# Dog_Fountain.net
KiCad netlist of a schematic drawn in EAGLE
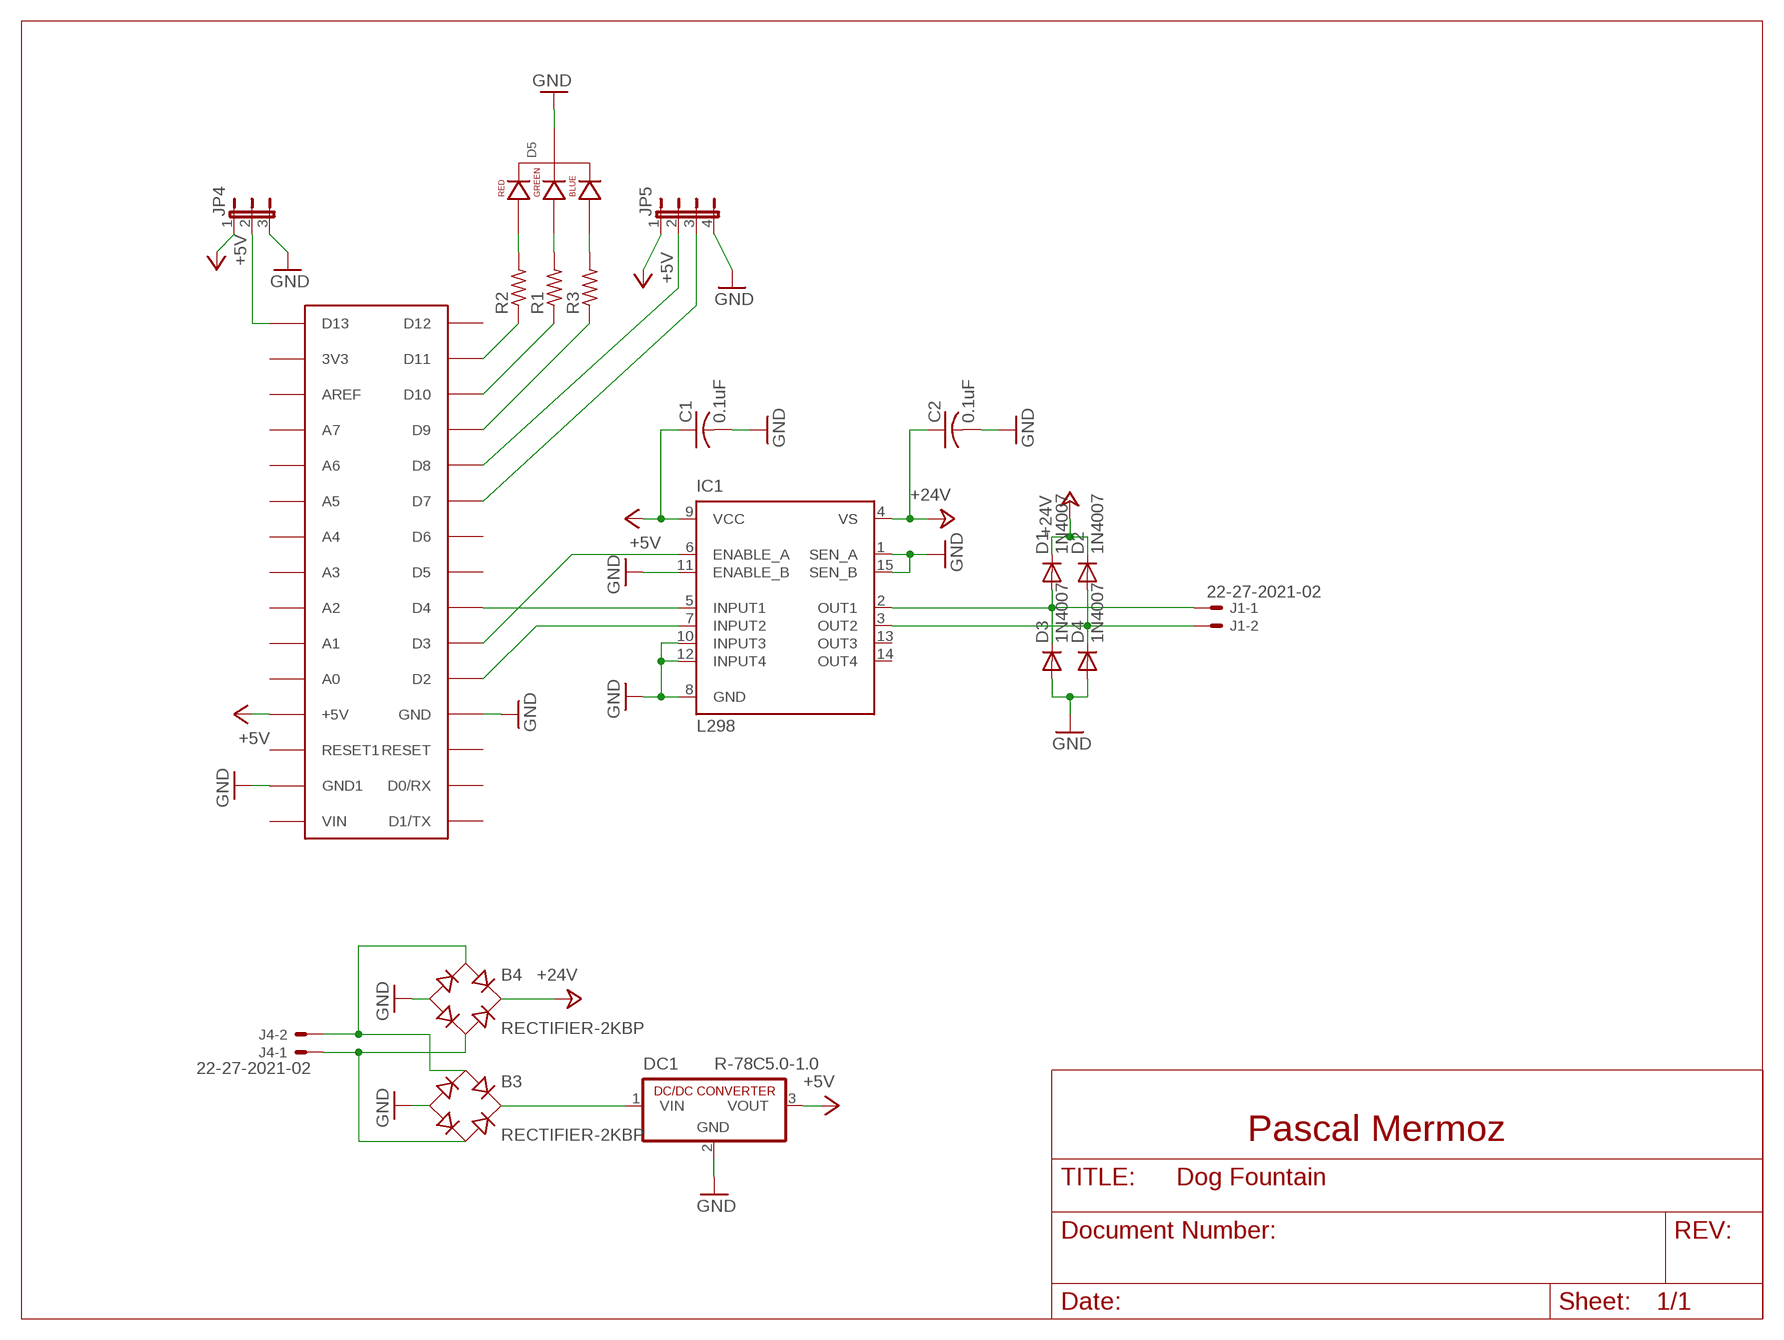
[diagram p0: schematic, sheet 1]

(export (version "E")
  (design (tool "Eeschema 10.0.6"))
  (components
    (comp (ref "B3")
      (value "RECTIFIER-2KBP")
      (footprint "eagle-import:2KBP")
      (fields (field (name "MPN") "KBP202G"))
      (libsource (lib "eagle-import") (part "RECTIFIER-2KBP"))
    )
    (comp (ref "B4")
      (value "RECTIFIER-2KBP")
      (footprint "eagle-import:2KBP")
      (fields (field (name "MPN") "KBP202G"))
      (libsource (lib "eagle-import") (part "RECTIFIER-2KBP"))
    )
    (comp (ref "C1")
      (value "0.1uF")
      (footprint "eagle-import:C050-024X044")
      (fields (field (name "MPN") "C317C104K5R5TA"))
      (libsource (lib "eagle-import") (part "C-US050-024X044"))
    )
    (comp (ref "C2")
      (value "0.1uF")
      (footprint "eagle-import:C050-024X044")
      (fields (field (name "MPN") "C317C104K5R5TA"))
      (libsource (lib "eagle-import") (part "C-US050-024X044"))
    )
    (comp (ref "D1")
      (value "1N4007")
      (footprint "eagle-import:DO41-10")
      (fields (field (name "MPN") "KBP202G"))
      (libsource (lib "eagle-import") (part "DIODE-DO41-10"))
    )
    (comp (ref "D2")
      (value "1N4007")
      (footprint "eagle-import:DO41-10")
      (fields (field (name "MPN") "KBP202G"))
      (libsource (lib "eagle-import") (part "DIODE-DO41-10"))
    )
    (comp (ref "D3")
      (value "1N4007")
      (footprint "eagle-import:DO41-10")
      (fields (field (name "MPN") "KBP202G"))
      (libsource (lib "eagle-import") (part "DIODE-DO41-10"))
    )
    (comp (ref "D4")
      (value "1N4007")
      (footprint "eagle-import:DO41-10")
      (fields (field (name "MPN") "KBP202G"))
      (libsource (lib "eagle-import") (part "DIODE-DO41-10"))
    )
    (comp (ref "D5")
      (value "LED-RGB-CC-THRUDIFFUSE")
      (footprint "eagle-import:LED-RGB-THRU")
      (libsource (lib "eagle-import") (part "LED-RGB-CC-THRUDIFFUSE"))
    )
    (comp (ref "DC1")
      (value "R-78C5.0-1.0")
      (footprint "eagle-import:SIP3")
      (fields (field (name "MPN") "OKI-78SR-5/1.5-W36-C"))
      (libsource (lib "eagle-import") (part "R-78C-1.05.0"))
    )
    (comp (ref "IC1")
      (value "L298")
      (footprint "eagle-import:MULTIWATT-15")
      (fields (field (name "MPN") "L298N"))
      (libsource (lib "eagle-import") (part "L298"))
    )
    (comp (ref "J1")
      (value "22-27-2021-02")
      (footprint "eagle-import:6410-02")
      (libsource (lib "eagle-import") (part "22-?-0227-2021"))
    )
    (comp (ref "J4")
      (value "22-27-2021-02")
      (footprint "eagle-import:6410-02")
      (libsource (lib "eagle-import") (part "22-?-0227-2021"))
    )
    (comp (ref "JP4")
      (value "JP2E")
      (footprint "eagle-import:JP2")
      (libsource (lib "eagle-import") (part "JP2E"))
    )
    (comp (ref "JP5")
      (value "JP4E")
      (footprint "eagle-import:JP4")
      (libsource (lib "eagle-import") (part "JP4E"))
    )
    (comp (ref "R1")
      (value "R-US_0204/2V")
      (footprint "eagle-import:0204V")
      (libsource (lib "eagle-import") (part "R-US_0204/2V"))
    )
    (comp (ref "R2")
      (value "R-US_0204/2V")
      (footprint "eagle-import:0204V")
      (libsource (lib "eagle-import") (part "R-US_0204/2V"))
    )
    (comp (ref "R3")
      (value "R-US_0204/2V")
      (footprint "eagle-import:0204V")
      (libsource (lib "eagle-import") (part "R-US_0204/2V"))
    )
    (comp (ref "U$1")
      (value "ARDUINONANO")
      (footprint "eagle-import:PDIP-32")
      (fields (field (name "MPN") "A000005"))
      (libsource (lib "eagle-import") (part "ARDUINONANO"))
    )
  )
  (nets
    (net (code "1") (name "+5V") (class "Default")
      (node (ref "C1") (pin "1") (pinfunction "1_1") (pintype "passive"))
      (node (ref "DC1") (pin "3") (pinfunction "VOUT_3") (pintype "passive"))
      (node (ref "IC1") (pin "9") (pinfunction "VCC_9") (pintype "power_in"))
      (node (ref "JP4") (pin "1") (pinfunction "1_1") (pintype "passive"))
      (node (ref "JP5") (pin "1") (pinfunction "1_1") (pintype "passive"))
      (node (ref "U$1") (pin "+5V") (pinfunction "+5V_+5V") (pintype "bidirectional"))
    )
    (net (code "2") (name "+24V") (class "Default")
      (node (ref "B4") (pin "+") (pinfunction "+_+") (pintype "passive"))
      (node (ref "C2") (pin "1") (pinfunction "1_1") (pintype "passive"))
      (node (ref "D1") (pin "C") (pinfunction "C_C") (pintype "passive"))
      (node (ref "D2") (pin "C") (pinfunction "C_C") (pintype "passive"))
      (node (ref "IC1") (pin "4") (pinfunction "VS_4") (pintype "power_in"))
    )
    (net (code "3") (name "GND") (class "Default")
      (node (ref "B3") (pin "-") (pinfunction "-_-") (pintype "passive"))
      (node (ref "B4") (pin "-") (pinfunction "-_-") (pintype "passive"))
      (node (ref "C1") (pin "2") (pinfunction "2_2") (pintype "passive"))
      (node (ref "C2") (pin "2") (pinfunction "2_2") (pintype "passive"))
      (node (ref "D3") (pin "A") (pinfunction "A_A") (pintype "passive"))
      (node (ref "D4") (pin "A") (pinfunction "A_A") (pintype "passive"))
      (node (ref "D5") (pin "2") (pinfunction "CATHODE_2") (pintype "bidirectional"))
      (node (ref "DC1") (pin "2") (pinfunction "GND_2") (pintype "passive"))
      (node (ref "IC1") (pin "1") (pinfunction "SEN_A_1") (pintype "input"))
      (node (ref "IC1") (pin "10") (pinfunction "INPUT3_10") (pintype "input"))
      (node (ref "IC1") (pin "11") (pinfunction "ENABLE_B_11") (pintype "input"))
      (node (ref "IC1") (pin "12") (pinfunction "INPUT4_12") (pintype "input"))
      (node (ref "IC1") (pin "15") (pinfunction "SEN_B_15") (pintype "input"))
      (node (ref "IC1") (pin "8") (pinfunction "GND_8") (pintype "power_in"))
      (node (ref "JP4") (pin "3") (pinfunction "3_3") (pintype "passive"))
      (node (ref "JP5") (pin "4") (pinfunction "4_4") (pintype "passive"))
      (node (ref "U$1") (pin "GND") (pinfunction "GND_GND") (pintype "bidirectional"))
      (node (ref "U$1") (pin "GND1") (pinfunction "GND1_GND1") (pintype "bidirectional"))
    )
    (net (code "4") (name "Net-(D5-BLUE_CATHODE)") (class "Default")
      (node (ref "D5") (pin "4") (pinfunction "BLUE_CATHODE_4") (pintype "bidirectional"))
      (node (ref "R3") (pin "2") (pinfunction "2_2") (pintype "passive"))
    )
    (net (code "5") (name "Net-(D5-GREEN_CATHODE)") (class "Default")
      (node (ref "D5") (pin "3") (pinfunction "GREEN_CATHODE_3") (pintype "bidirectional"))
      (node (ref "R1") (pin "2") (pinfunction "2_2") (pintype "passive"))
    )
    (net (code "6") (name "Net-(D5-RED_CATHODE)") (class "Default")
      (node (ref "D5") (pin "1") (pinfunction "RED_CATHODE_1") (pintype "bidirectional"))
      (node (ref "R2") (pin "2") (pinfunction "2_2") (pintype "passive"))
    )
    (net (code "7") (name "Net-(DC1-VIN)") (class "Default")
      (node (ref "B3") (pin "+") (pinfunction "+_+") (pintype "passive"))
      (node (ref "DC1") (pin "1") (pinfunction "VIN_1") (pintype "passive"))
    )
    (net (code "8") (name "Net-(IC1-ENABLE_A)") (class "Default")
      (node (ref "IC1") (pin "6") (pinfunction "ENABLE_A_6") (pintype "input"))
      (node (ref "U$1") (pin "D3") (pinfunction "D3_D3") (pintype "bidirectional"))
    )
    (net (code "9") (name "Net-(IC1-INPUT1)") (class "Default")
      (node (ref "IC1") (pin "5") (pinfunction "INPUT1_5") (pintype "input"))
      (node (ref "U$1") (pin "D4") (pinfunction "D4_D4") (pintype "bidirectional"))
    )
    (net (code "10") (name "Net-(IC1-INPUT2)") (class "Default")
      (node (ref "IC1") (pin "7") (pinfunction "INPUT2_7") (pintype "input"))
      (node (ref "U$1") (pin "D2") (pinfunction "D2_D2") (pintype "bidirectional"))
    )
    (net (code "11") (name "Net-(IC1-OUT1)") (class "Default")
      (node (ref "D1") (pin "A") (pinfunction "A_A") (pintype "passive"))
      (node (ref "D3") (pin "C") (pinfunction "C_C") (pintype "passive"))
      (node (ref "IC1") (pin "2") (pinfunction "OUT1_2") (pintype "output"))
      (node (ref "J1") (pin "1") (pinfunction "S_1") (pintype "passive"))
    )
    (net (code "12") (name "Net-(IC1-OUT2)") (class "Default")
      (node (ref "D2") (pin "A") (pinfunction "A_A") (pintype "passive"))
      (node (ref "D4") (pin "C") (pinfunction "C_C") (pintype "passive"))
      (node (ref "IC1") (pin "3") (pinfunction "OUT2_3") (pintype "output"))
      (node (ref "J1") (pin "2") (pinfunction "S_2") (pintype "passive"))
    )
    (net (code "13") (name "Net-(J4A-S)") (class "Default")
      (node (ref "B3") (pin "AC2") (pinfunction "AC2_AC2") (pintype "passive"))
      (node (ref "B4") (pin "AC2") (pinfunction "AC2_AC2") (pintype "passive"))
      (node (ref "J4") (pin "1") (pinfunction "S_1") (pintype "passive"))
    )
    (net (code "14") (name "Net-(J4B-S)") (class "Default")
      (node (ref "B3") (pin "AC1") (pinfunction "AC1_AC1") (pintype "passive"))
      (node (ref "B4") (pin "AC1") (pinfunction "AC1_AC1") (pintype "passive"))
      (node (ref "J4") (pin "2") (pinfunction "S_2") (pintype "passive"))
    )
    (net (code "15") (name "Net-(JP4-Pad2)") (class "Default")
      (node (ref "JP4") (pin "2") (pinfunction "2_2") (pintype "passive"))
      (node (ref "U$1") (pin "D13") (pinfunction "D13_D13") (pintype "bidirectional"))
    )
    (net (code "16") (name "Net-(JP5-Pad2)") (class "Default")
      (node (ref "JP5") (pin "2") (pinfunction "2_2") (pintype "passive"))
      (node (ref "U$1") (pin "D8") (pinfunction "D8_D8") (pintype "bidirectional"))
    )
    (net (code "17") (name "Net-(JP5-Pad3)") (class "Default")
      (node (ref "JP5") (pin "3") (pinfunction "3_3") (pintype "passive"))
      (node (ref "U$1") (pin "D7") (pinfunction "D7_D7") (pintype "bidirectional"))
    )
    (net (code "18") (name "Net-(R1-Pad1)") (class "Default")
      (node (ref "R1") (pin "1") (pinfunction "1_1") (pintype "passive"))
      (node (ref "U$1") (pin "D10") (pinfunction "D10_D10") (pintype "bidirectional"))
    )
    (net (code "19") (name "Net-(R2-Pad1)") (class "Default")
      (node (ref "R2") (pin "1") (pinfunction "1_1") (pintype "passive"))
      (node (ref "U$1") (pin "D11") (pinfunction "D11_D11") (pintype "bidirectional"))
    )
    (net (code "20") (name "Net-(R3-Pad1)") (class "Default")
      (node (ref "R3") (pin "1") (pinfunction "1_1") (pintype "passive"))
      (node (ref "U$1") (pin "D9") (pinfunction "D9_D9") (pintype "bidirectional"))
    )
    (net (code "21") (name "unconnected-(IC1-OUT3-Pad13)") (class "Default")
      (node (ref "IC1") (pin "13") (pinfunction "OUT3_13") (pintype "output"))
    )
    (net (code "22") (name "unconnected-(IC1-OUT4-Pad14)") (class "Default")
      (node (ref "IC1") (pin "14") (pinfunction "OUT4_14") (pintype "output"))
    )
    (net (code "23") (name "unconnected-(U$1-Pad3V3)") (class "Default")
      (node (ref "U$1") (pin "3V3") (pinfunction "3V3_3V3") (pintype "bidirectional"))
    )
    (net (code "24") (name "unconnected-(U$1-PadA0)") (class "Default")
      (node (ref "U$1") (pin "A0") (pinfunction "A0_A0") (pintype "bidirectional"))
    )
    (net (code "25") (name "unconnected-(U$1-PadA1)") (class "Default")
      (node (ref "U$1") (pin "A1") (pinfunction "A1_A1") (pintype "bidirectional"))
    )
    (net (code "26") (name "unconnected-(U$1-PadA2)") (class "Default")
      (node (ref "U$1") (pin "A2") (pinfunction "A2_A2") (pintype "bidirectional"))
    )
    (net (code "27") (name "unconnected-(U$1-PadA3)") (class "Default")
      (node (ref "U$1") (pin "A3") (pinfunction "A3_A3") (pintype "bidirectional"))
    )
    (net (code "28") (name "unconnected-(U$1-PadA4)") (class "Default")
      (node (ref "U$1") (pin "A4") (pinfunction "A4_A4") (pintype "bidirectional"))
    )
    (net (code "29") (name "unconnected-(U$1-PadA5)") (class "Default")
      (node (ref "U$1") (pin "A5") (pinfunction "A5_A5") (pintype "bidirectional"))
    )
    (net (code "30") (name "unconnected-(U$1-PadA6)") (class "Default")
      (node (ref "U$1") (pin "A6") (pinfunction "A6_A6") (pintype "bidirectional"))
    )
    (net (code "31") (name "unconnected-(U$1-PadA7)") (class "Default")
      (node (ref "U$1") (pin "A7") (pinfunction "A7_A7") (pintype "bidirectional"))
    )
    (net (code "32") (name "unconnected-(U$1-PadAREF)") (class "Default")
      (node (ref "U$1") (pin "AREF") (pinfunction "AREF_AREF") (pintype "bidirectional"))
    )
    (net (code "33") (name "unconnected-(U$1-PadD0{slash}RX)") (class "Default")
      (node (ref "U$1") (pin "D0/RX") (pinfunction "D0/RX_D0/RX") (pintype "bidirectional"))
    )
    (net (code "34") (name "unconnected-(U$1-PadD1{slash}TX)") (class "Default")
      (node (ref "U$1") (pin "D1/TX") (pinfunction "D1/TX_D1/TX") (pintype "bidirectional"))
    )
    (net (code "35") (name "unconnected-(U$1-PadD5)") (class "Default")
      (node (ref "U$1") (pin "D5") (pinfunction "D5_D5") (pintype "bidirectional"))
    )
    (net (code "36") (name "unconnected-(U$1-PadD6)") (class "Default")
      (node (ref "U$1") (pin "D6") (pinfunction "D6_D6") (pintype "bidirectional"))
    )
    (net (code "37") (name "unconnected-(U$1-PadD12)") (class "Default")
      (node (ref "U$1") (pin "D12") (pinfunction "D12_D12") (pintype "bidirectional"))
    )
    (net (code "38") (name "unconnected-(U$1-PadRESET)") (class "Default")
      (node (ref "U$1") (pin "RESET") (pinfunction "RESET_RESET") (pintype "bidirectional"))
    )
    (net (code "39") (name "unconnected-(U$1-PadRESET1)") (class "Default")
      (node (ref "U$1") (pin "RESET1") (pinfunction "RESET1_RESET1") (pintype "bidirectional"))
    )
    (net (code "40") (name "unconnected-(U$1-PadVIN)") (class "Default")
      (node (ref "U$1") (pin "VIN") (pinfunction "VIN_VIN") (pintype "bidirectional"))
    )
  )
)
